# Temperature_Sensor_Card_Digital.net
KiCad netlist of a schematic drawn in Altium Designer
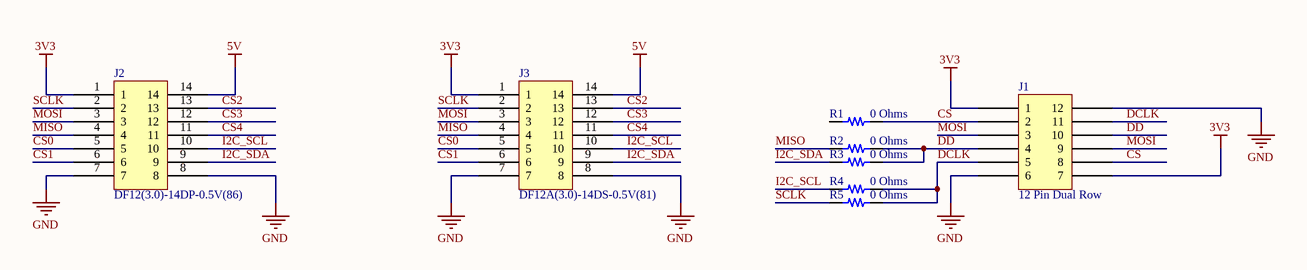
[diagram p0: Temperature Sensor Card Digital.SchDoc]

(export (version "E")
  (design (tool "Eeschema 10.0.6"))
  (components
    (comp (ref "J1")
      (value "12 Pin Dual Row")
      (footprint "TE 5650118-3 Card Edge")
      (libsource (lib "CelestialUseful") (part "12 Pin Dual Row"))
    )
    (comp (ref "J2")
      (value "DF12(3.0)-14DP-0.5V(86)")
      (footprint "HIROSE DF12 3.0-14DP-0.5V 86")
      (description "CONN HDR 14POS SMD GOLD")
      (fields (field (name "MANUFACTURER") "Hirose Electric Co Ltd"))
      (libsource (lib "altiumlibrary.com") (part "14 Pin Dual Row"))
    )
    (comp (ref "J3")
      (value "DF12A(3.0)-14DS-0.5V(81)")
      (footprint "HIROSE DF12A 3.0-14DS-0.5V 81")
      (description "CONN RCPT 14POS SMD GOLD")
      (fields (field (name "MANUFACTURER") "Hirose Electric Co Ltd"))
      (libsource (lib "altiumlibrary.com") (part "14 Pin Dual Row"))
    )
    (comp (ref "R1")
      (value "0 Ohms")
      (footprint "RES 0603_1608")
      (description "RES SMD 0 OHM JUMPER 1/10W 0603")
      (fields
        (field (name "PART NUMBER") "ERJ-3GEY0R00V")
        (field (name "MANUFACTURER") "Panasonic Electronic Components")
      )
      (libsource (lib "altiumlibrary.com") (part "Resistor"))
    )
    (comp (ref "R2")
      (value "0 Ohms")
      (footprint "RES 0603_1608")
      (description "RES SMD 0 OHM JUMPER 1/10W 0603")
      (fields
        (field (name "PART NUMBER") "ERJ-3GEY0R00V")
        (field (name "MANUFACTURER") "Panasonic Electronic Components")
      )
      (libsource (lib "altiumlibrary.com") (part "Resistor"))
    )
    (comp (ref "R3")
      (value "0 Ohms")
      (footprint "RES 0603_1608")
      (description "RES SMD 0 OHM JUMPER 1/10W 0603")
      (fields
        (field (name "PART NUMBER") "ERJ-3GEY0R00V")
        (field (name "MANUFACTURER") "Panasonic Electronic Components")
      )
      (libsource (lib "altiumlibrary.com") (part "Resistor"))
    )
    (comp (ref "R4")
      (value "0 Ohms")
      (footprint "RES 0603_1608")
      (description "RES SMD 0 OHM JUMPER 1/10W 0603")
      (fields
        (field (name "PART NUMBER") "ERJ-3GEY0R00V")
        (field (name "MANUFACTURER") "Panasonic Electronic Components")
      )
      (libsource (lib "altiumlibrary.com") (part "Resistor"))
    )
    (comp (ref "R5")
      (value "0 Ohms")
      (footprint "RES 0603_1608")
      (description "RES SMD 0 OHM JUMPER 1/10W 0603")
      (fields
        (field (name "PART NUMBER") "ERJ-3GEY0R00V")
        (field (name "MANUFACTURER") "Panasonic Electronic Components")
      )
      (libsource (lib "altiumlibrary.com") (part "Resistor"))
    )
  )
  (nets
    (net (code "1") (name "/CS") (class "Default")
      (node (ref "J1") (pin "2") (pinfunction "2_2") (pintype "passive"))
      (node (ref "J1") (pin "8") (pinfunction "8_8") (pintype "passive"))
      (node (ref "R1") (pin "2") (pinfunction "2_2") (pintype "passive"))
    )
    (net (code "2") (name "/CS0") (class "Default")
      (node (ref "J2") (pin "5") (pinfunction "5_5") (pintype "passive"))
      (node (ref "J3") (pin "5") (pinfunction "5_5") (pintype "passive"))
    )
    (net (code "3") (name "/CS1") (class "Default")
      (node (ref "J2") (pin "6") (pinfunction "6_6") (pintype "passive"))
      (node (ref "J3") (pin "6") (pinfunction "6_6") (pintype "passive"))
    )
    (net (code "4") (name "/CS2") (class "Default")
      (node (ref "J2") (pin "13") (pinfunction "13_13") (pintype "passive"))
      (node (ref "J3") (pin "13") (pinfunction "13_13") (pintype "passive"))
    )
    (net (code "5") (name "/CS3") (class "Default")
      (node (ref "J2") (pin "12") (pinfunction "12_12") (pintype "passive"))
      (node (ref "J3") (pin "12") (pinfunction "12_12") (pintype "passive"))
    )
    (net (code "6") (name "/CS4") (class "Default")
      (node (ref "J2") (pin "11") (pinfunction "11_11") (pintype "passive"))
      (node (ref "J3") (pin "11") (pinfunction "11_11") (pintype "passive"))
    )
    (net (code "7") (name "/DCLK") (class "Default")
      (node (ref "J1") (pin "11") (pinfunction "11_11") (pintype "passive"))
      (node (ref "J1") (pin "5") (pinfunction "5_5") (pintype "passive"))
      (node (ref "R4") (pin "2") (pinfunction "2_2") (pintype "passive"))
      (node (ref "R5") (pin "2") (pinfunction "2_2") (pintype "passive"))
    )
    (net (code "8") (name "/DD") (class "Default")
      (node (ref "J1") (pin "10") (pinfunction "10_10") (pintype "passive"))
      (node (ref "J1") (pin "4") (pinfunction "4_4") (pintype "passive"))
      (node (ref "R2") (pin "2") (pinfunction "2_2") (pintype "passive"))
      (node (ref "R3") (pin "2") (pinfunction "2_2") (pintype "passive"))
    )
    (net (code "9") (name "/I2C_SCL") (class "Default")
      (node (ref "J2") (pin "10") (pinfunction "10_10") (pintype "passive"))
      (node (ref "J3") (pin "10") (pinfunction "10_10") (pintype "passive"))
      (node (ref "R4") (pin "1") (pinfunction "1_1") (pintype "passive"))
    )
    (net (code "10") (name "/I2C_SDA") (class "Default")
      (node (ref "J2") (pin "9") (pinfunction "9_9") (pintype "passive"))
      (node (ref "J3") (pin "9") (pinfunction "9_9") (pintype "passive"))
      (node (ref "R3") (pin "1") (pinfunction "1_1") (pintype "passive"))
    )
    (net (code "11") (name "/MISO") (class "Default")
      (node (ref "J2") (pin "4") (pinfunction "4_4") (pintype "passive"))
      (node (ref "J3") (pin "4") (pinfunction "4_4") (pintype "passive"))
      (node (ref "R2") (pin "1") (pinfunction "1_1") (pintype "passive"))
    )
    (net (code "12") (name "/MOSI") (class "Default")
      (node (ref "J1") (pin "3") (pinfunction "3_3") (pintype "passive"))
      (node (ref "J1") (pin "9") (pinfunction "9_9") (pintype "passive"))
      (node (ref "J2") (pin "3") (pinfunction "3_3") (pintype "passive"))
      (node (ref "J3") (pin "3") (pinfunction "3_3") (pintype "passive"))
    )
    (net (code "13") (name "/SCLK") (class "Default")
      (node (ref "J2") (pin "2") (pinfunction "2_2") (pintype "passive"))
      (node (ref "J3") (pin "2") (pinfunction "2_2") (pintype "passive"))
      (node (ref "R5") (pin "1") (pinfunction "1_1") (pintype "passive"))
    )
    (net (code "14") (name "3V3") (class "Default")
      (node (ref "J1") (pin "1") (pinfunction "1_1") (pintype "passive"))
      (node (ref "J1") (pin "7") (pinfunction "7_7") (pintype "passive"))
      (node (ref "J2") (pin "1") (pinfunction "1_1") (pintype "passive"))
      (node (ref "J3") (pin "1") (pinfunction "1_1") (pintype "passive"))
    )
    (net (code "15") (name "5V") (class "Default")
      (node (ref "J2") (pin "14") (pinfunction "14_14") (pintype "passive"))
      (node (ref "J3") (pin "14") (pinfunction "14_14") (pintype "passive"))
    )
    (net (code "16") (name "GND") (class "Default")
      (node (ref "J1") (pin "12") (pinfunction "12_12") (pintype "passive"))
      (node (ref "J1") (pin "6") (pinfunction "6_6") (pintype "passive"))
      (node (ref "J2") (pin "7") (pinfunction "7_7") (pintype "passive"))
      (node (ref "J2") (pin "8") (pinfunction "8_8") (pintype "passive"))
      (node (ref "J3") (pin "7") (pinfunction "7_7") (pintype "passive"))
      (node (ref "J3") (pin "8") (pinfunction "8_8") (pintype "passive"))
    )
    (net (code "17") (name "unconnected-(R1-Pad1)") (class "Default")
      (node (ref "R1") (pin "1") (pinfunction "1_1") (pintype "passive"))
    )
  )
)
